# SWITCH.net
KiCad netlist of a schematic drawn in Altium Designer
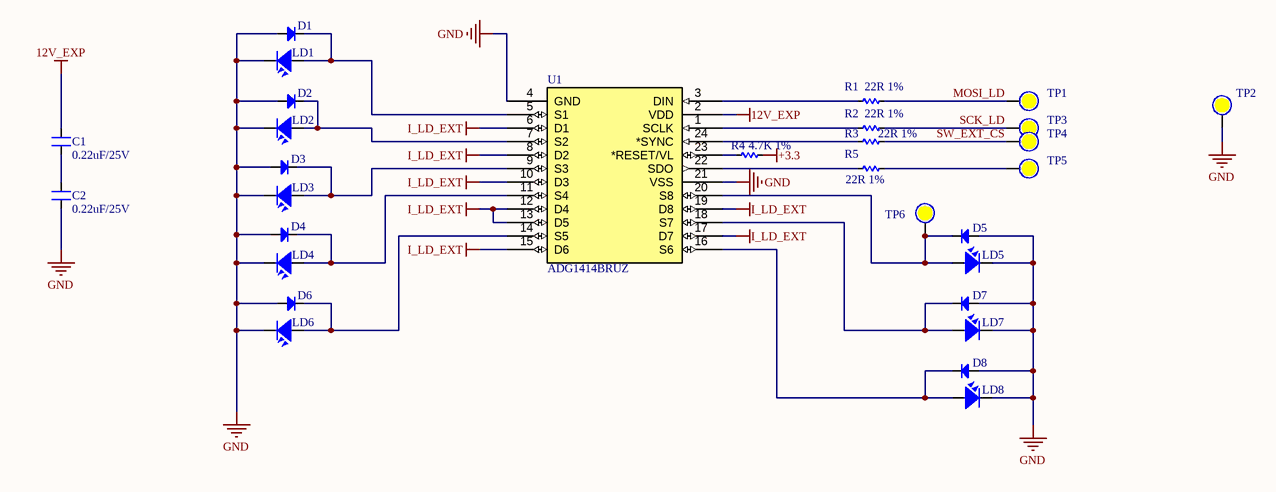
[diagram p0: SWITCH.SchDoc]

(export (version "E")
  (design (tool "Eeschema 10.0.6"))
  (components
    (comp (ref "C1")
      (value "0.22uF/25V")
      (footprint "CN-SMD-0603")
      (description "CAP CER 0.22UF 25V X7R 0603")
      (libsource (lib "SATELLITE_4U_LASER_EXT_1.4.0") (part "CN"))
    )
    (comp (ref "C2")
      (value "0.22uF/25V")
      (footprint "CN-SMD-0603")
      (description "CAP CER 0.22UF 25V X7R 0603")
      (libsource (lib "SATELLITE_4U_LASER_EXT_1.4.0") (part "CN"))
    )
    (comp (ref "D1")
      (value "1N4148W-TP")
      (footprint "SOD123")
      (description "DIODE STANDARD 100V 150MA SOD123")
      (fields (field (name "PUBLISHER") "Altium Limited"))
      (libsource (lib "SATELLITE_4U_LASER_EXT_1.4.0") (part "Diode SMD"))
    )
    (comp (ref "D2")
      (value "1N4148W-TP")
      (footprint "SOD123")
      (description "DIODE STANDARD 100V 150MA SOD123")
      (fields (field (name "PUBLISHER") "Altium Limited"))
      (libsource (lib "SATELLITE_4U_LASER_EXT_1.4.0") (part "Diode SMD"))
    )
    (comp (ref "D3")
      (value "1N4148W-TP")
      (footprint "SOD123")
      (description "DIODE STANDARD 100V 150MA SOD123")
      (fields (field (name "PUBLISHER") "Altium Limited"))
      (libsource (lib "SATELLITE_4U_LASER_EXT_1.4.0") (part "Diode SMD"))
    )
    (comp (ref "D4")
      (value "1N4148W-TP")
      (footprint "SOD123")
      (description "DIODE STANDARD 100V 150MA SOD123")
      (fields (field (name "PUBLISHER") "Altium Limited"))
      (libsource (lib "SATELLITE_4U_LASER_EXT_1.4.0") (part "Diode SMD"))
    )
    (comp (ref "D5")
      (value "1N4148W-TP")
      (footprint "SOD123")
      (description "DIODE STANDARD 100V 150MA SOD123")
      (fields (field (name "PUBLISHER") "Altium Limited"))
      (libsource (lib "SATELLITE_4U_LASER_EXT_1.4.0") (part "Diode SMD"))
    )
    (comp (ref "D6")
      (value "1N4148W-TP")
      (footprint "SOD123")
      (description "DIODE STANDARD 100V 150MA SOD123")
      (fields (field (name "PUBLISHER") "Altium Limited"))
      (libsource (lib "SATELLITE_4U_LASER_EXT_1.4.0") (part "Diode SMD"))
    )
    (comp (ref "D7")
      (value "1N4148W-TP")
      (footprint "SOD123")
      (description "DIODE STANDARD 100V 150MA SOD123")
      (fields (field (name "PUBLISHER") "Altium Limited"))
      (libsource (lib "SATELLITE_4U_LASER_EXT_1.4.0") (part "Diode SMD"))
    )
    (comp (ref "D8")
      (value "1N4148W-TP")
      (footprint "SOD123")
      (description "DIODE STANDARD 100V 150MA SOD123")
      (fields (field (name "PUBLISHER") "Altium Limited"))
      (libsource (lib "SATELLITE_4U_LASER_EXT_1.4.0") (part "Diode SMD"))
    )
    (comp (ref "LD1")
      (value "LaserDiode")
      (footprint "laser")
      (libsource (lib "SATELLITE_4U_LASER_EXT_1.4.0") (part "LASER"))
    )
    (comp (ref "LD2")
      (value "LaserDiode")
      (footprint "laser")
      (libsource (lib "SATELLITE_4U_LASER_EXT_1.4.0") (part "LASER"))
    )
    (comp (ref "LD3")
      (value "LaserDiode")
      (footprint "laser")
      (libsource (lib "SATELLITE_4U_LASER_EXT_1.4.0") (part "LASER"))
    )
    (comp (ref "LD4")
      (value "LaserDiode")
      (footprint "laser")
      (libsource (lib "SATELLITE_4U_LASER_EXT_1.4.0") (part "LASER"))
    )
    (comp (ref "LD5")
      (value "LaserDiode")
      (footprint "laser")
      (libsource (lib "SATELLITE_4U_LASER_EXT_1.4.0") (part "LASER"))
    )
    (comp (ref "LD6")
      (value "LaserDiode")
      (footprint "laser")
      (libsource (lib "SATELLITE_4U_LASER_EXT_1.4.0") (part "LASER"))
    )
    (comp (ref "LD7")
      (value "LaserDiode")
      (footprint "laser")
      (libsource (lib "SATELLITE_4U_LASER_EXT_1.4.0") (part "LASER"))
    )
    (comp (ref "LD8")
      (value "LaserDiode")
      (footprint "laser")
      (libsource (lib "SATELLITE_4U_LASER_EXT_1.4.0") (part "LASER"))
    )
    (comp (ref "R1")
      (value "22R 1%")
      (footprint "RES-SMD-0603")
      (description "Resistor")
      (fields
        (field (name "MANUFACTURER") "Generic Components")
        (field (name "PUBLISHER") "Altium Hobart Technology Centre")
      )
      (libsource (lib "SATELLITE_4U_LASER_EXT_1.4.0") (part "Res-SMD"))
    )
    (comp (ref "R2")
      (value "22R 1%")
      (footprint "RES-SMD-0603")
      (description "Resistor")
      (fields
        (field (name "MANUFACTURER") "Generic Components")
        (field (name "PUBLISHER") "Altium Hobart Technology Centre")
      )
      (libsource (lib "SATELLITE_4U_LASER_EXT_1.4.0") (part "Res-SMD"))
    )
    (comp (ref "R3")
      (value "22R 1%")
      (footprint "RES-SMD-0603")
      (description "Resistor")
      (fields
        (field (name "MANUFACTURER") "Generic Components")
        (field (name "PUBLISHER") "Altium Hobart Technology Centre")
      )
      (libsource (lib "SATELLITE_4U_LASER_EXT_1.4.0") (part "Res-SMD"))
    )
    (comp (ref "R4")
      (value "4.7K 1%")
      (footprint "RES-SMD-0603")
      (description "RES SMD 4.7K OHM 1% 1/10W 0603")
      (fields
        (field (name "MANUFACTURER") "Generic Components")
        (field (name "PUBLISHER") "Altium Hobart Technology Centre")
      )
      (libsource (lib "SATELLITE_4U_LASER_EXT_1.4.0") (part "Res-SMD"))
    )
    (comp (ref "R5")
      (value "22R 1%")
      (footprint "RES-SMD-0603")
      (description "Resistor")
      (fields
        (field (name "MANUFACTURER") "Generic Components")
        (field (name "PUBLISHER") "Altium Hobart Technology Centre")
      )
      (libsource (lib "SATELLITE_4U_LASER_EXT_1.4.0") (part "Res-SMD"))
    )
    (comp (ref "TP1")
      (value "~")
      (footprint "TESTPOINT")
      (description "Test Point")
      (libsource (lib "SATELLITE_4U_LASER_EXT_1.4.0") (part "Test Point"))
    )
    (comp (ref "TP2")
      (value "~")
      (footprint "TESTPOINT")
      (description "Test Point")
      (libsource (lib "") (part "Test Point_1"))
    )
    (comp (ref "TP3")
      (value "~")
      (footprint "TESTPOINT")
      (description "Test Point")
      (libsource (lib "SATELLITE_4U_LASER_EXT_1.4.0") (part "Test Point"))
    )
    (comp (ref "TP4")
      (value "~")
      (footprint "TESTPOINT")
      (description "Test Point")
      (libsource (lib "SATELLITE_4U_LASER_EXT_1.4.0") (part "Test Point"))
    )
    (comp (ref "TP5")
      (value "~")
      (footprint "TESTPOINT")
      (description "Test Point")
      (libsource (lib "SATELLITE_4U_LASER_EXT_1.4.0") (part "Test Point"))
    )
    (comp (ref "TP6")
      (value "~")
      (footprint "TESTPOINT")
      (description "Test Point")
      (libsource (lib "") (part "Test Point_1"))
    )
    (comp (ref "U1")
      (value "ADG1414BRUZ")
      (footprint "TSSOP24")
      (description "IC SW SPST-NOX8 11.5OHM 24TSSOP")
      (libsource (lib "SATELLITE_4U_LASER_EXT_1.4.0") (part "ADG1414BRUZ"))
    )
  )
  (nets
    (net (code "1") (name "+3.3") (class "Default")
      (node (ref "R4") (pin "1") (pinfunction "1_1") (pintype "passive"))
    )
    (net (code "2") (name "/MOSI_LD") (class "Default")
      (node (ref "R1") (pin "1") (pinfunction "1_1") (pintype "passive"))
      (node (ref "TP1") (pin "1") (pinfunction "1_1") (pintype "passive"))
    )
    (net (code "3") (name "/SCK_LD") (class "Default")
      (node (ref "R2") (pin "1") (pinfunction "1_1") (pintype "passive"))
      (node (ref "TP3") (pin "1") (pinfunction "1_1") (pintype "passive"))
    )
    (net (code "4") (name "/SW_EXT_CS") (class "Default")
      (node (ref "R3") (pin "1") (pinfunction "1_1") (pintype "passive"))
      (node (ref "TP4") (pin "1") (pinfunction "1_1") (pintype "passive"))
    )
    (net (code "5") (name "12V_EXP") (class "Default")
      (node (ref "C1") (pin "2") (pinfunction "2_2") (pintype "passive"))
      (node (ref "U1") (pin "2") (pinfunction "VDD_2") (pintype "power_in"))
    )
    (net (code "6") (name "GND") (class "Default")
      (node (ref "C2") (pin "1") (pinfunction "1_1") (pintype "passive"))
      (node (ref "D1") (pin "1") (pinfunction "A_1") (pintype "passive"))
      (node (ref "D2") (pin "1") (pinfunction "A_1") (pintype "passive"))
      (node (ref "D3") (pin "1") (pinfunction "A_1") (pintype "passive"))
      (node (ref "D4") (pin "1") (pinfunction "A_1") (pintype "passive"))
      (node (ref "D5") (pin "1") (pinfunction "A_1") (pintype "passive"))
      (node (ref "D6") (pin "1") (pinfunction "A_1") (pintype "passive"))
      (node (ref "D7") (pin "1") (pinfunction "A_1") (pintype "passive"))
      (node (ref "D8") (pin "1") (pinfunction "A_1") (pintype "passive"))
      (node (ref "LD1") (pin "3") (pinfunction "3_3") (pintype "passive"))
      (node (ref "LD2") (pin "3") (pinfunction "3_3") (pintype "passive"))
      (node (ref "LD3") (pin "3") (pinfunction "3_3") (pintype "passive"))
      (node (ref "LD4") (pin "3") (pinfunction "3_3") (pintype "passive"))
      (node (ref "LD5") (pin "3") (pinfunction "3_3") (pintype "passive"))
      (node (ref "LD6") (pin "3") (pinfunction "3_3") (pintype "passive"))
      (node (ref "LD7") (pin "3") (pinfunction "3_3") (pintype "passive"))
      (node (ref "LD8") (pin "3") (pinfunction "3_3") (pintype "passive"))
      (node (ref "TP2") (pin "1") (pinfunction "1_1") (pintype "passive"))
      (node (ref "U1") (pin "21") (pinfunction "VSS_21") (pintype "power_in"))
      (node (ref "U1") (pin "4") (pinfunction "GND_4") (pintype "power_in"))
    )
    (net (code "7") (name "I_LD_EXT") (class "Default")
      (node (ref "U1") (pin "10") (pinfunction "D3_10") (pintype "bidirectional"))
      (node (ref "U1") (pin "12") (pinfunction "D4_12") (pintype "bidirectional"))
      (node (ref "U1") (pin "13") (pinfunction "D5_13") (pintype "bidirectional"))
      (node (ref "U1") (pin "15") (pinfunction "D6_15") (pintype "bidirectional"))
      (node (ref "U1") (pin "17") (pinfunction "D7_17") (pintype "bidirectional"))
      (node (ref "U1") (pin "19") (pinfunction "D8_19") (pintype "bidirectional"))
      (node (ref "U1") (pin "6") (pinfunction "D1_6") (pintype "bidirectional"))
      (node (ref "U1") (pin "8") (pinfunction "D2_8") (pintype "bidirectional"))
    )
    (net (code "8") (name "Net-(C1-Pad1)") (class "Default")
      (node (ref "C1") (pin "1") (pinfunction "1_1") (pintype "passive"))
      (node (ref "C2") (pin "2") (pinfunction "2_2") (pintype "passive"))
    )
    (net (code "9") (name "Net-(D1-K)") (class "Default")
      (node (ref "D1") (pin "2") (pinfunction "K_2") (pintype "passive"))
      (node (ref "LD1") (pin "1") (pinfunction "1_1") (pintype "passive"))
      (node (ref "U1") (pin "5") (pinfunction "S1_5") (pintype "bidirectional"))
    )
    (net (code "10") (name "Net-(D2-K)") (class "Default")
      (node (ref "D2") (pin "2") (pinfunction "K_2") (pintype "passive"))
      (node (ref "LD2") (pin "1") (pinfunction "1_1") (pintype "passive"))
      (node (ref "U1") (pin "7") (pinfunction "S2_7") (pintype "bidirectional"))
    )
    (net (code "11") (name "Net-(D3-K)") (class "Default")
      (node (ref "D3") (pin "2") (pinfunction "K_2") (pintype "passive"))
      (node (ref "LD3") (pin "1") (pinfunction "1_1") (pintype "passive"))
      (node (ref "U1") (pin "9") (pinfunction "S3_9") (pintype "bidirectional"))
    )
    (net (code "12") (name "Net-(D4-K)") (class "Default")
      (node (ref "D4") (pin "2") (pinfunction "K_2") (pintype "passive"))
      (node (ref "LD4") (pin "1") (pinfunction "1_1") (pintype "passive"))
      (node (ref "U1") (pin "11") (pinfunction "S4_11") (pintype "bidirectional"))
    )
    (net (code "13") (name "Net-(D5-K)") (class "Default")
      (node (ref "D5") (pin "2") (pinfunction "K_2") (pintype "passive"))
      (node (ref "LD5") (pin "1") (pinfunction "1_1") (pintype "passive"))
      (node (ref "TP6") (pin "1") (pinfunction "1_1") (pintype "passive"))
      (node (ref "U1") (pin "20") (pinfunction "S8_20") (pintype "bidirectional"))
    )
    (net (code "14") (name "Net-(D6-K)") (class "Default")
      (node (ref "D6") (pin "2") (pinfunction "K_2") (pintype "passive"))
      (node (ref "LD6") (pin "1") (pinfunction "1_1") (pintype "passive"))
      (node (ref "U1") (pin "14") (pinfunction "S5_14") (pintype "bidirectional"))
    )
    (net (code "15") (name "Net-(D7-K)") (class "Default")
      (node (ref "D7") (pin "2") (pinfunction "K_2") (pintype "passive"))
      (node (ref "LD7") (pin "1") (pinfunction "1_1") (pintype "passive"))
      (node (ref "U1") (pin "18") (pinfunction "S7_18") (pintype "bidirectional"))
    )
    (net (code "16") (name "Net-(D8-K)") (class "Default")
      (node (ref "D8") (pin "2") (pinfunction "K_2") (pintype "passive"))
      (node (ref "LD8") (pin "1") (pinfunction "1_1") (pintype "passive"))
      (node (ref "U1") (pin "16") (pinfunction "S6_16") (pintype "bidirectional"))
    )
    (net (code "17") (name "Net-(R5-Pad1)") (class "Default")
      (node (ref "R5") (pin "1") (pinfunction "1_1") (pintype "passive"))
      (node (ref "TP5") (pin "1") (pinfunction "1_1") (pintype "passive"))
    )
    (net (code "18") (name "Net-(U1-*RESET{slash}VL)") (class "Default")
      (node (ref "R4") (pin "2") (pinfunction "2_2") (pintype "passive"))
      (node (ref "U1") (pin "23") (pinfunction "*RESET/VL_23") (pintype "bidirectional"))
    )
    (net (code "19") (name "Net-(U1-*SYNC)") (class "Default")
      (node (ref "R3") (pin "2") (pinfunction "2_2") (pintype "passive"))
      (node (ref "U1") (pin "24") (pinfunction "*SYNC_24") (pintype "input"))
    )
    (net (code "20") (name "Net-(U1-DIN)") (class "Default")
      (node (ref "R1") (pin "2") (pinfunction "2_2") (pintype "passive"))
      (node (ref "U1") (pin "3") (pinfunction "DIN_3") (pintype "input"))
    )
    (net (code "21") (name "Net-(U1-SCLK)") (class "Default")
      (node (ref "R2") (pin "2") (pinfunction "2_2") (pintype "passive"))
      (node (ref "U1") (pin "1") (pinfunction "SCLK_1") (pintype "input"))
    )
    (net (code "22") (name "Net-(U1-SDO)") (class "Default")
      (node (ref "R5") (pin "2") (pinfunction "2_2") (pintype "passive"))
      (node (ref "U1") (pin "22") (pinfunction "SDO_22") (pintype "output"))
    )
  )
)
